# maze_1.net
KiCad netlist of a schematic drawn in EAGLE
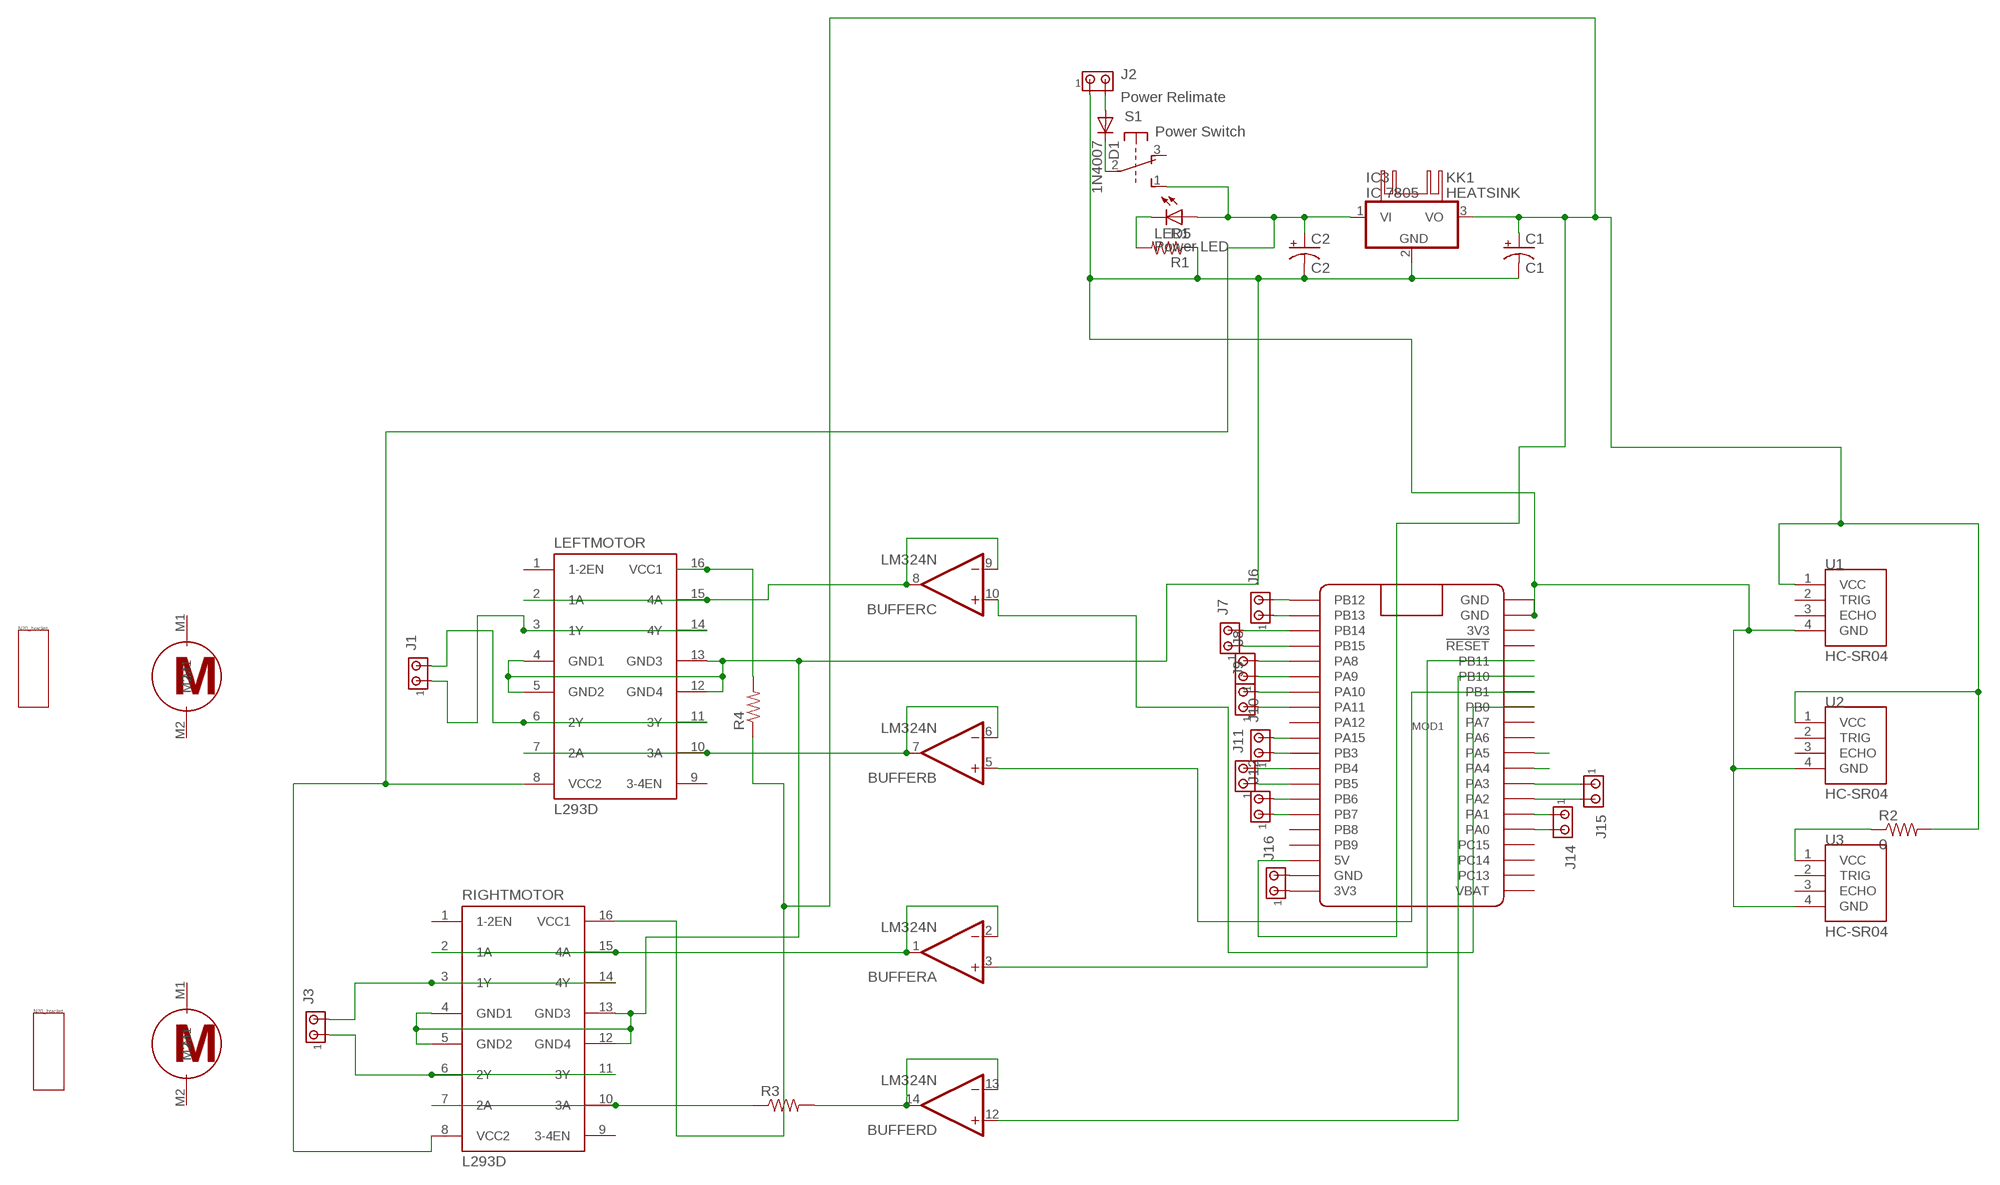
[diagram p0: schematic, sheet 1]

(export (version "E")
  (design (tool "Eeschema 10.0.6"))
  (components
    (comp (ref "BUFFER")
      (value "LM324N")
      (footprint "eagle-import:DIL14")
      (libsource (lib "eagle-import") (part "LM324N"))
    )
    (comp (ref "C1")
      (value "C1")
      (footprint "eagle-import:CPOL-RADIAL-5MM-10MM")
      (libsource (lib "eagle-import") (part "1000UF-RADIAL-5MM-25V-20%"))
    )
    (comp (ref "C2")
      (value "C2")
      (footprint "eagle-import:E3,5-8")
      (libsource (lib "eagle-import") (part "CPOL-USE3.5-8"))
    )
    (comp (ref "D1")
      (value "1N4007")
      (footprint "eagle-import:DO41-10")
      (libsource (lib "eagle-import") (part "1N4004"))
    )
    (comp (ref "IC3")
      (value "IC 7805")
      (footprint "eagle-import:TO220V")
      (libsource (lib "eagle-import") (part "78TV05"))
    )
    (comp (ref "J1")
      (value "MTA02-100")
      (footprint "eagle-import:10X02MTA")
      (libsource (lib "eagle-import") (part "con-amp_127_MTA02-100"))
    )
    (comp (ref "J2")
      (value "Power Relimate")
      (footprint "eagle-import:10X02MTA")
      (libsource (lib "eagle-import") (part "MTA02-100"))
    )
    (comp (ref "J3")
      (value "MTA02-100")
      (footprint "eagle-import:10X02MTA")
      (libsource (lib "eagle-import") (part "con-amp_127_MTA02-100"))
    )
    (comp (ref "J6")
      (value "MTA02-100")
      (footprint "eagle-import:10X02MTA")
      (libsource (lib "eagle-import") (part "con-amp_127_MTA02-100"))
    )
    (comp (ref "J7")
      (value "MTA02-100")
      (footprint "eagle-import:10X02MTA")
      (libsource (lib "eagle-import") (part "con-amp_127_MTA02-100"))
    )
    (comp (ref "J8")
      (value "MTA02-100")
      (footprint "eagle-import:10X02MTA")
      (libsource (lib "eagle-import") (part "con-amp_127_MTA02-100"))
    )
    (comp (ref "J9")
      (value "MTA02-100")
      (footprint "eagle-import:10X02MTA")
      (libsource (lib "eagle-import") (part "con-amp_127_MTA02-100"))
    )
    (comp (ref "J10")
      (value "MTA02-100")
      (footprint "eagle-import:10X02MTA")
      (libsource (lib "eagle-import") (part "con-amp_127_MTA02-100"))
    )
    (comp (ref "J11")
      (value "MTA02-100")
      (footprint "eagle-import:10X02MTA")
      (libsource (lib "eagle-import") (part "con-amp_127_MTA02-100"))
    )
    (comp (ref "J12")
      (value "MTA02-100")
      (footprint "eagle-import:10X02MTA")
      (libsource (lib "eagle-import") (part "con-amp_127_MTA02-100"))
    )
    (comp (ref "J14")
      (value "MTA02-100")
      (footprint "eagle-import:10X02MTA")
      (libsource (lib "eagle-import") (part "con-amp_127_MTA02-100"))
    )
    (comp (ref "J15")
      (value "MTA02-100")
      (footprint "eagle-import:10X02MTA")
      (libsource (lib "eagle-import") (part "con-amp_127_MTA02-100"))
    )
    (comp (ref "J16")
      (value "MTA02-100")
      (footprint "eagle-import:10X02MTA")
      (libsource (lib "eagle-import") (part "con-amp_127_MTA02-100"))
    )
    (comp (ref "KK1")
      (value "HEATSINK")
      (footprint "eagle-import:HEATSINK")
      (libsource (lib "eagle-import") (part "HEATSINK"))
    )
    (comp (ref "LED5")
      (value "Power LED")
      (footprint "eagle-import:LED3MM")
      (libsource (lib "eagle-import") (part "LED3MM"))
    )
    (comp (ref "LEFTMOTOR")
      (value "L293D")
      (footprint "eagle-import:DIL16")
      (libsource (lib "eagle-import") (part "L293D"))
    )
    (comp (ref "MOD1")
      (value "BLUE_PILL")
      (footprint "eagle-import:BLUE_PILL")
      (libsource (lib "eagle-import") (part "BLUE_PILL"))
    )
    (comp (ref "R1")
      (value "R1")
      (footprint "eagle-import:0204_7")
      (libsource (lib "eagle-import") (part "R-US_0204/7"))
    )
    (comp (ref "R2")
      (value "0")
      (footprint "eagle-import:0204_7")
      (libsource (lib "eagle-import") (part "R-US_0204/7"))
    )
    (comp (ref "R3")
      (value "R-US_0204/7")
      (footprint "eagle-import:0204_7")
      (libsource (lib "eagle-import") (part "R-US_0204/7"))
    )
    (comp (ref "R4")
      (value "R-US_0204/7")
      (footprint "eagle-import:0204_7")
      (libsource (lib "eagle-import") (part "R-US_0204/7"))
    )
    (comp (ref "RIGHTMOTOR")
      (value "L293D")
      (footprint "eagle-import:DIL16")
      (libsource (lib "eagle-import") (part "L293D"))
    )
    (comp (ref "S1")
      (value "Power Switch")
      (footprint "eagle-import:9077-2")
      (libsource (lib "eagle-import") (part "9077-2"))
    )
    (comp (ref "U$1")
      (value "MOTOR_N20")
      (footprint "eagle-import:MOTOR_N20")
      (libsource (lib "eagle-import") (part "MOTOR_N20"))
    )
    (comp (ref "U$2")
      (value "MOTOR_N20")
      (footprint "eagle-import:MOTOR_N20")
      (libsource (lib "eagle-import") (part "MOTOR_N20"))
    )
    (comp (ref "U$4")
      (value "N20_BRACKET")
      (footprint "eagle-import:BRACKER")
      (libsource (lib "eagle-import") (part "N20_BRACKET"))
    )
    (comp (ref "U$5")
      (value "N20_BRACKET")
      (footprint "eagle-import:BRACKER")
      (libsource (lib "eagle-import") (part "N20_BRACKET"))
    )
    (comp (ref "U1")
      (value "HC-SR04")
      (footprint "eagle-import:XCVR_HC-SR04")
      (fields (field (name "MF") "OSEPP Electronics"))
      (libsource (lib "eagle-import") (part "HC-SR04"))
    )
    (comp (ref "U2")
      (value "HC-SR04")
      (footprint "eagle-import:XCVR_HC-SR04")
      (fields (field (name "MF") "OSEPP Electronics"))
      (libsource (lib "eagle-import") (part "HC-SR04"))
    )
    (comp (ref "U3")
      (value "HC-SR04")
      (footprint "eagle-import:XCVR_HC-SR04")
      (fields (field (name "MF") "OSEPP Electronics"))
      (libsource (lib "eagle-import") (part "HC-SR04"))
    )
  )
  (nets
    (net (code "1") (name "Net-(BUFFERA-+IN)") (class "Default")
      (node (ref "BUFFER") (pin "3") (pinfunction "+IN_3") (pintype "input"))
      (node (ref "MOD1") (pin "P$25") (pinfunction "PB11_P$25") (pintype "bidirectional"))
    )
    (net (code "2") (name "Net-(BUFFERA--IN)") (class "Default")
      (node (ref "BUFFER") (pin "1") (pinfunction "OUT_1") (pintype "output"))
      (node (ref "BUFFER") (pin "2") (pinfunction "-IN_2") (pintype "input"))
      (node (ref "RIGHTMOTOR") (pin "15") (pinfunction "4A_15") (pintype "input"))
      (node (ref "RIGHTMOTOR") (pin "2") (pinfunction "1A_2") (pintype "input"))
    )
    (net (code "3") (name "Net-(BUFFERB-+IN)") (class "Default")
      (node (ref "BUFFER") (pin "5") (pinfunction "+IN_5") (pintype "input"))
      (node (ref "MOD1") (pin "P$27") (pinfunction "PB1_P$27") (pintype "bidirectional"))
    )
    (net (code "4") (name "Net-(BUFFERB--IN)") (class "Default")
      (node (ref "BUFFER") (pin "6") (pinfunction "-IN_6") (pintype "input"))
      (node (ref "BUFFER") (pin "7") (pinfunction "OUT_7") (pintype "output"))
      (node (ref "LEFTMOTOR") (pin "10") (pinfunction "3A_10") (pintype "input"))
      (node (ref "LEFTMOTOR") (pin "7") (pinfunction "2A_7") (pintype "input"))
    )
    (net (code "5") (name "Net-(BUFFERC-+IN)") (class "Default")
      (node (ref "BUFFER") (pin "10") (pinfunction "+IN_10") (pintype "input"))
      (node (ref "MOD1") (pin "P$28") (pinfunction "PB0_P$28") (pintype "bidirectional"))
    )
    (net (code "6") (name "Net-(BUFFERC--IN)") (class "Default")
      (node (ref "BUFFER") (pin "8") (pinfunction "OUT_8") (pintype "output"))
      (node (ref "BUFFER") (pin "9") (pinfunction "-IN_9") (pintype "input"))
      (node (ref "LEFTMOTOR") (pin "15") (pinfunction "4A_15") (pintype "input"))
      (node (ref "LEFTMOTOR") (pin "2") (pinfunction "1A_2") (pintype "input"))
    )
    (net (code "7") (name "Net-(BUFFERD-+IN)") (class "Default")
      (node (ref "BUFFER") (pin "12") (pinfunction "+IN_12") (pintype "input"))
      (node (ref "MOD1") (pin "P$26") (pinfunction "PB10_P$26") (pintype "bidirectional"))
    )
    (net (code "8") (name "Net-(BUFFERD--IN)") (class "Default")
      (node (ref "BUFFER") (pin "13") (pinfunction "-IN_13") (pintype "input"))
      (node (ref "BUFFER") (pin "14") (pinfunction "OUT_14") (pintype "output"))
      (node (ref "R3") (pin "2") (pinfunction "2_2") (pintype "passive"))
    )
    (net (code "9") (name "Net-(D1-PadA)") (class "Default")
      (node (ref "D1") (pin "A") (pinfunction "A_A") (pintype "passive"))
      (node (ref "J2") (pin "2") (pinfunction "2_2") (pintype "passive"))
    )
    (net (code "10") (name "Net-(IC3-GND)") (class "Default")
      (node (ref "C1") (pin "-") (pinfunction "-_-") (pintype "passive"))
      (node (ref "C2") (pin "-") (pinfunction "-_-") (pintype "passive"))
      (node (ref "IC3") (pin "2") (pinfunction "GND_2") (pintype "passive"))
      (node (ref "J2") (pin "1") (pinfunction "1_1") (pintype "passive"))
      (node (ref "LEFTMOTOR") (pin "12") (pinfunction "GND4_12") (pintype "power_in"))
      (node (ref "LEFTMOTOR") (pin "13") (pinfunction "GND3_13") (pintype "power_in"))
      (node (ref "LEFTMOTOR") (pin "4") (pinfunction "GND1_4") (pintype "power_in"))
      (node (ref "LEFTMOTOR") (pin "5") (pinfunction "GND2_5") (pintype "power_in"))
      (node (ref "MOD1") (pin "P$21") (pinfunction "GND_P$21") (pintype "passive"))
      (node (ref "MOD1") (pin "P$22") (pinfunction "GND_P$22") (pintype "passive"))
      (node (ref "R1") (pin "1") (pinfunction "1_1") (pintype "passive"))
      (node (ref "RIGHTMOTOR") (pin "12") (pinfunction "GND4_12") (pintype "power_in"))
      (node (ref "RIGHTMOTOR") (pin "13") (pinfunction "GND3_13") (pintype "power_in"))
      (node (ref "RIGHTMOTOR") (pin "4") (pinfunction "GND1_4") (pintype "power_in"))
      (node (ref "RIGHTMOTOR") (pin "5") (pinfunction "GND2_5") (pintype "power_in"))
      (node (ref "U1") (pin "4") (pinfunction "GND_4") (pintype "power_in"))
      (node (ref "U2") (pin "4") (pinfunction "GND_4") (pintype "power_in"))
      (node (ref "U3") (pin "4") (pinfunction "GND_4") (pintype "power_in"))
    )
    (net (code "11") (name "Net-(IC3-VI)") (class "Default")
      (node (ref "C2") (pin "+") (pinfunction "+_+") (pintype "passive"))
      (node (ref "IC3") (pin "1") (pinfunction "VI_1") (pintype "input"))
      (node (ref "LED5") (pin "A") (pinfunction "A_A") (pintype "passive"))
      (node (ref "LEFTMOTOR") (pin "8") (pinfunction "VCC2_8") (pintype "power_in"))
      (node (ref "RIGHTMOTOR") (pin "8") (pinfunction "VCC2_8") (pintype "power_in"))
      (node (ref "S1") (pin "1") (pinfunction "S_1") (pintype "passive"))
    )
    (net (code "12") (name "Net-(IC3-VO)") (class "Default")
      (node (ref "C1") (pin "+") (pinfunction "+_+") (pintype "passive"))
      (node (ref "IC3") (pin "3") (pinfunction "VO_3") (pintype "passive"))
      (node (ref "MOD1") (pin "P$18") (pinfunction "5V_P$18") (pintype "bidirectional"))
      (node (ref "R2") (pin "2") (pinfunction "2_2") (pintype "passive"))
      (node (ref "R4") (pin "1") (pinfunction "1_1") (pintype "passive"))
      (node (ref "RIGHTMOTOR") (pin "16") (pinfunction "VCC1_16") (pintype "power_in"))
      (node (ref "U1") (pin "1") (pinfunction "VCC_1") (pintype "power_in"))
      (node (ref "U2") (pin "1") (pinfunction "VCC_1") (pintype "power_in"))
    )
    (net (code "13") (name "Net-(J16-Pad1)") (class "Default")
      (node (ref "J16") (pin "1") (pinfunction "1_1") (pintype "passive"))
      (node (ref "MOD1") (pin "P$20") (pinfunction "3V3_P$20") (pintype "bidirectional"))
    )
    (net (code "14") (name "Net-(J16-Pad2)") (class "Default")
      (node (ref "J16") (pin "2") (pinfunction "2_2") (pintype "passive"))
      (node (ref "MOD1") (pin "P$19") (pinfunction "GND_P$19") (pintype "passive"))
    )
    (net (code "15") (name "Net-(LED5-C)") (class "Default")
      (node (ref "LED5") (pin "K") (pinfunction "C_K") (pintype "passive"))
      (node (ref "R1") (pin "2") (pinfunction "2_2") (pintype "passive"))
    )
    (net (code "16") (name "Net-(LEFTMOTOR-1Y)") (class "Default")
      (node (ref "J1") (pin "1") (pinfunction "1_1") (pintype "passive"))
      (node (ref "LEFTMOTOR") (pin "14") (pinfunction "4Y_14") (pintype "output"))
      (node (ref "LEFTMOTOR") (pin "3") (pinfunction "1Y_3") (pintype "output"))
    )
    (net (code "17") (name "Net-(LEFTMOTOR-2Y)") (class "Default")
      (node (ref "J1") (pin "2") (pinfunction "2_2") (pintype "passive"))
      (node (ref "LEFTMOTOR") (pin "11") (pinfunction "3Y_11") (pintype "output"))
      (node (ref "LEFTMOTOR") (pin "6") (pinfunction "2Y_6") (pintype "output"))
    )
    (net (code "18") (name "Net-(LEFTMOTOR-VCC1)") (class "Default")
      (node (ref "LEFTMOTOR") (pin "16") (pinfunction "VCC1_16") (pintype "power_in"))
      (node (ref "R4") (pin "2") (pinfunction "2_2") (pintype "passive"))
    )
    (net (code "19") (name "Net-(MOD1-PA0)") (class "Default")
      (node (ref "J14") (pin "2") (pinfunction "2_2") (pintype "passive"))
      (node (ref "MOD1") (pin "P$36") (pinfunction "PA0_P$36") (pintype "bidirectional"))
    )
    (net (code "20") (name "Net-(MOD1-PA1)") (class "Default")
      (node (ref "J14") (pin "1") (pinfunction "1_1") (pintype "passive"))
      (node (ref "MOD1") (pin "P$35") (pinfunction "PA1_P$35") (pintype "bidirectional"))
    )
    (net (code "21") (name "Net-(MOD1-PA2)") (class "Default")
      (node (ref "J15") (pin "2") (pinfunction "2_2") (pintype "passive"))
      (node (ref "MOD1") (pin "P$34") (pinfunction "PA2_P$34") (pintype "bidirectional"))
    )
    (net (code "22") (name "Net-(MOD1-PA3)") (class "Default")
      (node (ref "J15") (pin "1") (pinfunction "1_1") (pintype "passive"))
      (node (ref "MOD1") (pin "P$33") (pinfunction "PA3_P$33") (pintype "bidirectional"))
    )
    (net (code "23") (name "Net-(MOD1-PA8)") (class "Default")
      (node (ref "J8") (pin "2") (pinfunction "2_2") (pintype "passive"))
      (node (ref "MOD1") (pin "P$5") (pinfunction "PA8_P$5") (pintype "bidirectional"))
    )
    (net (code "24") (name "Net-(MOD1-PA9)") (class "Default")
      (node (ref "J8") (pin "1") (pinfunction "1_1") (pintype "passive"))
      (node (ref "MOD1") (pin "P$6") (pinfunction "PA9_P$6") (pintype "bidirectional"))
    )
    (net (code "25") (name "Net-(MOD1-PA10)") (class "Default")
      (node (ref "J9") (pin "2") (pinfunction "2_2") (pintype "passive"))
      (node (ref "MOD1") (pin "P$7") (pinfunction "PA10_P$7") (pintype "bidirectional"))
    )
    (net (code "26") (name "Net-(MOD1-PA11)") (class "Default")
      (node (ref "J9") (pin "1") (pinfunction "1_1") (pintype "passive"))
      (node (ref "MOD1") (pin "P$8") (pinfunction "PA11_P$8") (pintype "bidirectional"))
    )
    (net (code "27") (name "Net-(MOD1-PA15)") (class "Default")
      (node (ref "J10") (pin "2") (pinfunction "2_2") (pintype "passive"))
      (node (ref "MOD1") (pin "P$10") (pinfunction "PA15_P$10") (pintype "bidirectional"))
    )
    (net (code "28") (name "Net-(MOD1-PB3)") (class "Default")
      (node (ref "J10") (pin "1") (pinfunction "1_1") (pintype "passive"))
      (node (ref "MOD1") (pin "P$11") (pinfunction "PB3_P$11") (pintype "bidirectional"))
    )
    (net (code "29") (name "Net-(MOD1-PB4)") (class "Default")
      (node (ref "J11") (pin "2") (pinfunction "2_2") (pintype "passive"))
      (node (ref "MOD1") (pin "P$12") (pinfunction "PB4_P$12") (pintype "bidirectional"))
    )
    (net (code "30") (name "Net-(MOD1-PB5)") (class "Default")
      (node (ref "J11") (pin "1") (pinfunction "1_1") (pintype "passive"))
      (node (ref "MOD1") (pin "P$13") (pinfunction "PB5_P$13") (pintype "bidirectional"))
    )
    (net (code "31") (name "Net-(MOD1-PB6)") (class "Default")
      (node (ref "J12") (pin "2") (pinfunction "2_2") (pintype "passive"))
      (node (ref "MOD1") (pin "P$14") (pinfunction "PB6_P$14") (pintype "bidirectional"))
    )
    (net (code "32") (name "Net-(MOD1-PB7)") (class "Default")
      (node (ref "J12") (pin "1") (pinfunction "1_1") (pintype "passive"))
      (node (ref "MOD1") (pin "P$15") (pinfunction "PB7_P$15") (pintype "bidirectional"))
    )
    (net (code "33") (name "Net-(MOD1-PB12)") (class "Default")
      (node (ref "J6") (pin "2") (pinfunction "2_2") (pintype "passive"))
      (node (ref "MOD1") (pin "P$1") (pinfunction "PB12_P$1") (pintype "bidirectional"))
    )
    (net (code "34") (name "Net-(MOD1-PB13)") (class "Default")
      (node (ref "J6") (pin "1") (pinfunction "1_1") (pintype "passive"))
      (node (ref "MOD1") (pin "P$2") (pinfunction "PB13_P$2") (pintype "bidirectional"))
    )
    (net (code "35") (name "Net-(MOD1-PB14)") (class "Default")
      (node (ref "J7") (pin "2") (pinfunction "2_2") (pintype "passive"))
      (node (ref "MOD1") (pin "P$3") (pinfunction "PB14_P$3") (pintype "bidirectional"))
    )
    (net (code "36") (name "Net-(MOD1-PB15)") (class "Default")
      (node (ref "J7") (pin "1") (pinfunction "1_1") (pintype "passive"))
      (node (ref "MOD1") (pin "P$4") (pinfunction "PB15_P$4") (pintype "bidirectional"))
    )
    (net (code "37") (name "Net-(RIGHTMOTOR-1Y)") (class "Default")
      (node (ref "J3") (pin "2") (pinfunction "2_2") (pintype "passive"))
      (node (ref "RIGHTMOTOR") (pin "14") (pinfunction "4Y_14") (pintype "output"))
      (node (ref "RIGHTMOTOR") (pin "3") (pinfunction "1Y_3") (pintype "output"))
    )
    (net (code "38") (name "Net-(RIGHTMOTOR-2A)") (class "Default")
      (node (ref "R3") (pin "1") (pinfunction "1_1") (pintype "passive"))
      (node (ref "RIGHTMOTOR") (pin "10") (pinfunction "3A_10") (pintype "input"))
      (node (ref "RIGHTMOTOR") (pin "7") (pinfunction "2A_7") (pintype "input"))
    )
    (net (code "39") (name "Net-(RIGHTMOTOR-2Y)") (class "Default")
      (node (ref "J3") (pin "1") (pinfunction "1_1") (pintype "passive"))
      (node (ref "RIGHTMOTOR") (pin "11") (pinfunction "3Y_11") (pintype "output"))
      (node (ref "RIGHTMOTOR") (pin "6") (pinfunction "2Y_6") (pintype "output"))
    )
    (net (code "40") (name "Net-(S1A-P)") (class "Default")
      (node (ref "D1") (pin "C") (pinfunction "C_C") (pintype "passive"))
      (node (ref "S1") (pin "2") (pinfunction "P_2") (pintype "passive"))
    )
    (net (code "41") (name "Net-(U3-VCC)") (class "Default")
      (node (ref "R2") (pin "1") (pinfunction "1_1") (pintype "passive"))
      (node (ref "U3") (pin "1") (pinfunction "VCC_1") (pintype "power_in"))
    )
    (net (code "42") (name "unconnected-(LEFTMOTOR-1-2EN-Pad1)") (class "Default")
      (node (ref "LEFTMOTOR") (pin "1") (pinfunction "1-2EN_1") (pintype "input"))
    )
    (net (code "43") (name "unconnected-(LEFTMOTOR-3-4EN-Pad9)") (class "Default")
      (node (ref "LEFTMOTOR") (pin "9") (pinfunction "3-4EN_9") (pintype "input"))
    )
    (net (code "44") (name "unconnected-(MOD1-3V3-PadP$23)") (class "Default")
      (node (ref "MOD1") (pin "P$23") (pinfunction "3V3_P$23") (pintype "bidirectional"))
    )
    (net (code "45") (name "unconnected-(MOD1-PA4-PadP$32)") (class "Default")
      (node (ref "MOD1") (pin "P$32") (pinfunction "PA4_P$32") (pintype "bidirectional"))
    )
    (net (code "46") (name "unconnected-(MOD1-PA5-PadP$31)") (class "Default")
      (node (ref "MOD1") (pin "P$31") (pinfunction "PA5_P$31") (pintype "bidirectional"))
    )
    (net (code "47") (name "unconnected-(MOD1-PA6-PadP$30)") (class "Default")
      (node (ref "MOD1") (pin "P$30") (pinfunction "PA6_P$30") (pintype "bidirectional"))
    )
    (net (code "48") (name "unconnected-(MOD1-PA7-PadP$29)") (class "Default")
      (node (ref "MOD1") (pin "P$29") (pinfunction "PA7_P$29") (pintype "bidirectional"))
    )
    (net (code "49") (name "unconnected-(MOD1-PA12-PadP$9)") (class "Default")
      (node (ref "MOD1") (pin "P$9") (pinfunction "PA12_P$9") (pintype "bidirectional"))
    )
    (net (code "50") (name "unconnected-(MOD1-PB8-PadP$16)") (class "Default")
      (node (ref "MOD1") (pin "P$16") (pinfunction "PB8_P$16") (pintype "bidirectional"))
    )
    (net (code "51") (name "unconnected-(MOD1-PB9-PadP$17)") (class "Default")
      (node (ref "MOD1") (pin "P$17") (pinfunction "PB9_P$17") (pintype "bidirectional"))
    )
    (net (code "52") (name "unconnected-(MOD1-PC13-PadP$39)") (class "Default")
      (node (ref "MOD1") (pin "P$39") (pinfunction "PC13_P$39") (pintype "bidirectional"))
    )
    (net (code "53") (name "unconnected-(MOD1-PC14-PadP$38)") (class "Default")
      (node (ref "MOD1") (pin "P$38") (pinfunction "PC14_P$38") (pintype "bidirectional"))
    )
    (net (code "54") (name "unconnected-(MOD1-PC15-PadP$37)") (class "Default")
      (node (ref "MOD1") (pin "P$37") (pinfunction "PC15_P$37") (pintype "bidirectional"))
    )
    (net (code "55") (name "unconnected-(MOD1-VBAT-PadP$40)") (class "Default")
      (node (ref "MOD1") (pin "P$40") (pinfunction "VBAT_P$40") (pintype "bidirectional"))
    )
    (net (code "56") (name "unconnected-(MOD1-~{RESET}-PadP$24)") (class "Default")
      (node (ref "MOD1") (pin "P$24") (pinfunction "~{RESET}_P$24") (pintype "bidirectional"))
    )
    (net (code "57") (name "unconnected-(RIGHTMOTOR-1-2EN-Pad1)") (class "Default")
      (node (ref "RIGHTMOTOR") (pin "1") (pinfunction "1-2EN_1") (pintype "input"))
    )
    (net (code "58") (name "unconnected-(RIGHTMOTOR-3-4EN-Pad9)") (class "Default")
      (node (ref "RIGHTMOTOR") (pin "9") (pinfunction "3-4EN_9") (pintype "input"))
    )
    (net (code "59") (name "unconnected-(S1A-O-Pad3)") (class "Default")
      (node (ref "S1") (pin "3") (pinfunction "O_3") (pintype "passive"))
    )
    (net (code "60") (name "unconnected-(U$1-PadM1)") (class "Default")
      (node (ref "U$1") (pin "M1") (pinfunction "M1_M1") (pintype "bidirectional"))
    )
    (net (code "61") (name "unconnected-(U$1-PadM2)") (class "Default")
      (node (ref "U$1") (pin "M2") (pinfunction "M2_M2") (pintype "bidirectional"))
    )
    (net (code "62") (name "unconnected-(U$2-PadM1)") (class "Default")
      (node (ref "U$2") (pin "M1") (pinfunction "M1_M1") (pintype "bidirectional"))
    )
    (net (code "63") (name "unconnected-(U$2-PadM2)") (class "Default")
      (node (ref "U$2") (pin "M2") (pinfunction "M2_M2") (pintype "bidirectional"))
    )
    (net (code "64") (name "unconnected-(U1-ECHO-Pad3)") (class "Default")
      (node (ref "U1") (pin "3") (pinfunction "ECHO_3") (pintype "bidirectional"))
    )
    (net (code "65") (name "unconnected-(U1-TRIG-Pad2)") (class "Default")
      (node (ref "U1") (pin "2") (pinfunction "TRIG_2") (pintype "bidirectional"))
    )
    (net (code "66") (name "unconnected-(U2-ECHO-Pad3)") (class "Default")
      (node (ref "U2") (pin "3") (pinfunction "ECHO_3") (pintype "bidirectional"))
    )
    (net (code "67") (name "unconnected-(U2-TRIG-Pad2)") (class "Default")
      (node (ref "U2") (pin "2") (pinfunction "TRIG_2") (pintype "bidirectional"))
    )
    (net (code "68") (name "unconnected-(U3-ECHO-Pad3)") (class "Default")
      (node (ref "U3") (pin "3") (pinfunction "ECHO_3") (pintype "bidirectional"))
    )
    (net (code "69") (name "unconnected-(U3-TRIG-Pad2)") (class "Default")
      (node (ref "U3") (pin "2") (pinfunction "TRIG_2") (pintype "bidirectional"))
    )
  )
)
